# JBC_245.net
KiCad netlist of a schematic drawn in Altium Designer
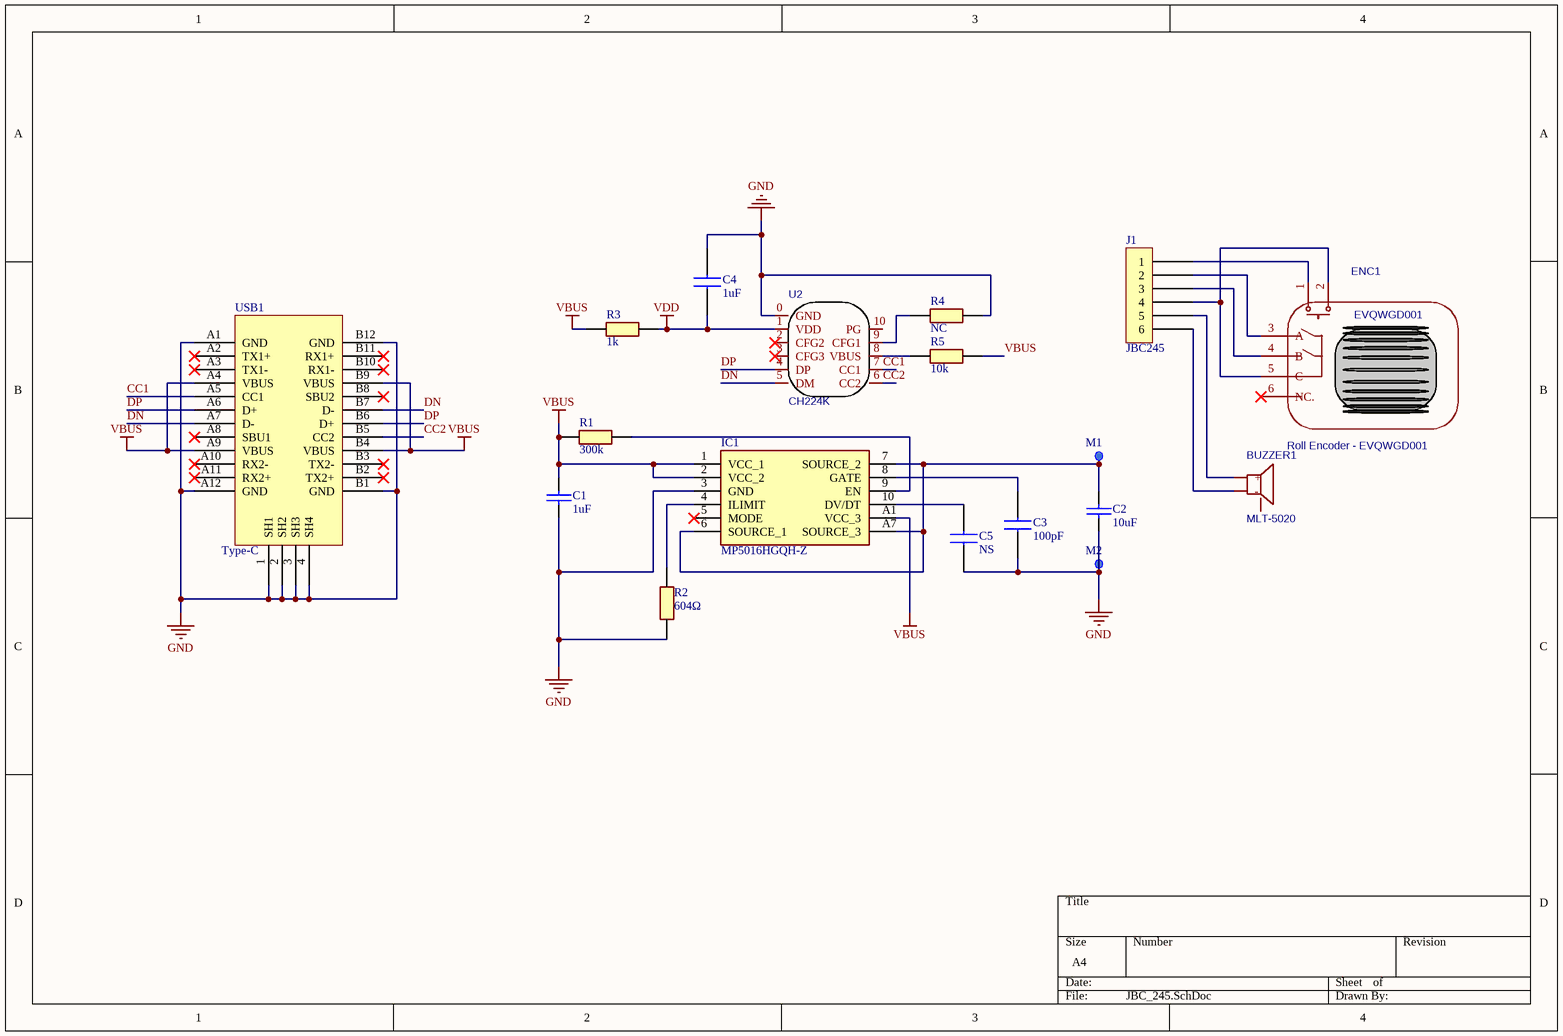
[diagram p0: JBC_245.SchDoc]

(export (version "E")
  (design (tool "Eeschema 10.0.6"))
  (components
    (comp (ref "BUZZER1")
      (value "MLT-5020")
      (footprint "BUZ-SMD_3P-L5.2-W5.2-P3.50-BR")
      (description "Buzzer")
      (fields (field (name "BOM_SUPPLIER PART") "C94598"))
      (libsource (lib "SFT_V4") (part "MLT-5020"))
    )
    (comp (ref "C1")
      (value "1uF")
      (footprint "1206C")
      (description "无极性电容")
      (libsource (lib "电容") (part "CAP"))
    )
    (comp (ref "C2")
      (value "10uF")
      (footprint "1206C")
      (description "无极性电容")
      (libsource (lib "电容") (part "CAP"))
    )
    (comp (ref "C3")
      (value "100pF")
      (footprint "CAP_0402")
      (description "Capacitor")
      (fields
        (field (name "MANUFACTURER_PART_NUMBER") "0402YC104MAT2A")
        (field (name "MOUSER PART NUMBER") "581-0402YC104MAT2A")
      )
      (libsource (lib "SFT_V4") (part "0402YC104MAT2A"))
    )
    (comp (ref "C4")
      (value "1uF")
      (footprint "CAP_0402")
      (description "Capacitor")
      (fields
        (field (name "MANUFACTURER_PART_NUMBER") "0402YC104MAT2A")
        (field (name "MOUSER PART NUMBER") "581-0402YC104MAT2A")
      )
      (libsource (lib "SFT_V4") (part "0402YC104MAT2A"))
    )
    (comp (ref "C5")
      (value "NS")
      (footprint "CAP_0402")
      (description "Capacitor")
      (fields
        (field (name "MANUFACTURER_PART_NUMBER") "0402YC104MAT2A")
        (field (name "MOUSER PART NUMBER") "581-0402YC104MAT2A")
      )
      (libsource (lib "SFT_V4") (part "0402YC104MAT2A"))
    )
    (comp (ref "IC1")
      (value "MP5016HGQH-Z")
      (footprint "MP5016HGQHZ")
      (description "Integrated Circuit")
      (fields (field (name "MOUSER PART NUMBER") "946-MP5016HGQH-Z"))
      (libsource (lib "SFT_V4") (part "MP5016HGQH-Z"))
    )
    (comp (ref "J1")
      (value "JBC245")
      (footprint "JBC_245_Connect")
      (libsource (lib "SFT_V4") (part "JBC_245_Connect"))
    )
    (comp (ref "M1") (value "Test_Point") (footprint "TP-PIN") (libsource (lib "SFT_V4") (part "Test_Point")))
    (comp (ref "M2") (value "Test_Point") (footprint "TP-PIN") (libsource (lib "SFT_V4") (part "Test_Point")))
    (comp (ref "R1")
      (value "300k")
      (footprint "RES_0402")
      (description "Resistor")
      (fields
        (field (name "MANUFACTURER_PART_NUMBER") "RC0402JR-1320RL")
        (field (name "MOUSER PART NUMBER") "603-RC0402JR-1320RL")
      )
      (libsource (lib "") (part "RC0402JR-1320RL_1"))
    )
    (comp (ref "R2")
      (value "604Ω")
      (footprint "RES_0402")
      (description "Resistor")
      (fields
        (field (name "MANUFACTURER_PART_NUMBER") "RC0402JR-1320RL")
        (field (name "MOUSER PART NUMBER") "603-RC0402JR-1320RL")
      )
      (libsource (lib "SFT_V4") (part "RC0402JR-1320RL"))
    )
    (comp (ref "R3")
      (value "1k")
      (footprint "RES_0402")
      (description "Resistor")
      (fields
        (field (name "MANUFACTURER_PART_NUMBER") "RC0402JR-1320RL")
        (field (name "MOUSER PART NUMBER") "603-RC0402JR-1320RL")
      )
      (libsource (lib "") (part "RC0402JR-1320RL_1"))
    )
    (comp (ref "R4")
      (value "NC")
      (footprint "RES_0402")
      (description "Resistor")
      (fields
        (field (name "MANUFACTURER_PART_NUMBER") "RC0402JR-1320RL")
        (field (name "MOUSER PART NUMBER") "603-RC0402JR-1320RL")
      )
      (libsource (lib "") (part "RC0402JR-1320RL_1"))
    )
    (comp (ref "R5")
      (value "10k")
      (footprint "RES_0402")
      (description "Resistor")
      (fields
        (field (name "MANUFACTURER_PART_NUMBER") "RC0402JR-1320RL")
        (field (name "MOUSER PART NUMBER") "603-RC0402JR-1320RL")
      )
      (libsource (lib "") (part "RC0402JR-1320RL_1"))
    )
    (comp (ref "U1")
      (value "Roll Encoder - EVQWGD001")
      (footprint "EVQWGD001 ENCODER")
      (fields (field (name "BOM_MANUFACTURER PART") "EVQWGD001") (field (name "CONTRIBUTOR") "ChristAlix"))
      (libsource (lib "My_AD_Lib") (part "Roll Encoder - EVQWGD001"))
    )
    (comp (ref "U2")
      (value "CH224K")
      (footprint "ESSOP-10_L5.0-W3.9")
      (fields (field (name "CONTRIBUTOR") "小茅"))
      (libsource (lib "My_AD_Lib") (part "CH224K"))
    )
    (comp (ref "USB1")
      (value "Type-C")
      (footprint "Type-C-TOP")
      (libsource (lib "SFT_V4") (part "USB-Type-C-TOP"))
    )
  )
  (nets
    (net (code "1") (name "/CC1") (class "Default")
      (node (ref "U2") (pin "7") (pinfunction "CC1_7") (pintype "passive"))
      (node (ref "USB1") (pin "A5") (pinfunction "CC1_A5") (pintype "passive"))
    )
    (net (code "2") (name "/CC2") (class "Default")
      (node (ref "U2") (pin "6") (pinfunction "CC2_6") (pintype "passive"))
      (node (ref "USB1") (pin "B5") (pinfunction "CC2_B5") (pintype "passive"))
    )
    (net (code "3") (name "/DN") (class "Default")
      (node (ref "U2") (pin "5") (pinfunction "DM_5") (pintype "passive"))
      (node (ref "USB1") (pin "A7") (pinfunction "D-_A7") (pintype "passive"))
      (node (ref "USB1") (pin "B7") (pinfunction "D-_B7") (pintype "passive"))
    )
    (net (code "4") (name "/DP") (class "Default")
      (node (ref "U2") (pin "4") (pinfunction "DP_4") (pintype "passive"))
      (node (ref "USB1") (pin "A6") (pinfunction "D+_A6") (pintype "passive"))
      (node (ref "USB1") (pin "B6") (pinfunction "D+_B6") (pintype "passive"))
    )
    (net (code "5") (name "GND") (class "Default")
      (node (ref "C1") (pin "1") (pinfunction "1_1") (pintype "passive"))
      (node (ref "C2") (pin "1") (pinfunction "1_1") (pintype "passive"))
      (node (ref "C3") (pin "1") (pinfunction "1_1") (pintype "passive"))
      (node (ref "C4") (pin "2") (pinfunction "2_2") (pintype "passive"))
      (node (ref "C5") (pin "1") (pinfunction "1_1") (pintype "passive"))
      (node (ref "IC1") (pin "3") (pinfunction "GND_3") (pintype "passive"))
      (node (ref "M2") (pin "1") (pinfunction "1_1") (pintype "passive"))
      (node (ref "R2") (pin "1") (pinfunction "1_1") (pintype "passive"))
      (node (ref "R4") (pin "2") (pinfunction "2_2") (pintype "passive"))
      (node (ref "U2") (pin "0") (pinfunction "GND_0") (pintype "passive"))
      (node (ref "USB1") (pin "1") (pinfunction "SH1_1") (pintype "passive"))
      (node (ref "USB1") (pin "2") (pinfunction "SH2_2") (pintype "passive"))
      (node (ref "USB1") (pin "3") (pinfunction "SH3_3") (pintype "passive"))
      (node (ref "USB1") (pin "4") (pinfunction "SH4_4") (pintype "passive"))
      (node (ref "USB1") (pin "A1") (pinfunction "GND_A1") (pintype "passive"))
      (node (ref "USB1") (pin "A12") (pinfunction "GND_A12") (pintype "passive"))
      (node (ref "USB1") (pin "B1") (pinfunction "GND_B1") (pintype "passive"))
      (node (ref "USB1") (pin "B12") (pinfunction "GND_B12") (pintype "passive"))
    )
    (net (code "6") (name "Net-(BUZZER1-+)") (class "Default")
      (node (ref "BUZZER1") (pin "2") (pinfunction "+_2") (pintype "passive"))
      (node (ref "J1") (pin "5") (pinfunction "5_5") (pintype "passive"))
    )
    (net (code "7") (name "Net-(BUZZER1--)") (class "Default")
      (node (ref "BUZZER1") (pin "3") (pinfunction "-_3") (pintype "passive"))
      (node (ref "J1") (pin "6") (pinfunction "6_6") (pintype "passive"))
    )
    (net (code "8") (name "Net-(IC1-DV{slash}DT)") (class "Default")
      (node (ref "C5") (pin "2") (pinfunction "2_2") (pintype "passive"))
      (node (ref "IC1") (pin "10") (pinfunction "DV/DT_10") (pintype "passive"))
    )
    (net (code "9") (name "Net-(IC1-EN)") (class "Default")
      (node (ref "IC1") (pin "9") (pinfunction "EN_9") (pintype "passive"))
      (node (ref "R1") (pin "2") (pinfunction "2_2") (pintype "passive"))
    )
    (net (code "10") (name "Net-(IC1-GATE)") (class "Default")
      (node (ref "C3") (pin "2") (pinfunction "2_2") (pintype "passive"))
      (node (ref "IC1") (pin "8") (pinfunction "GATE_8") (pintype "passive"))
    )
    (net (code "11") (name "Net-(IC1-ILIMIT)") (class "Default")
      (node (ref "IC1") (pin "4") (pinfunction "ILIMIT_4") (pintype "passive"))
      (node (ref "R2") (pin "2") (pinfunction "2_2") (pintype "passive"))
    )
    (net (code "12") (name "Net-(IC1-SOURCE_1)") (class "Default")
      (node (ref "C2") (pin "2") (pinfunction "2_2") (pintype "passive"))
      (node (ref "IC1") (pin "6") (pinfunction "SOURCE_1_6") (pintype "passive"))
      (node (ref "IC1") (pin "7") (pinfunction "SOURCE_2_7") (pintype "passive"))
      (node (ref "IC1") (pin "A7") (pinfunction "SOURCE_3_A7") (pintype "passive"))
      (node (ref "M1") (pin "1") (pinfunction "1_1") (pintype "passive"))
    )
    (net (code "13") (name "Net-(U1-A)") (class "Default")
      (node (ref "J1") (pin "2") (pinfunction "2_2") (pintype "passive"))
      (node (ref "U1") (pin "3") (pinfunction "A_3") (pintype "passive"))
    )
    (net (code "14") (name "Net-(U1-B)") (class "Default")
      (node (ref "J1") (pin "3") (pinfunction "3_3") (pintype "passive"))
      (node (ref "U1") (pin "4") (pinfunction "B_4") (pintype "passive"))
    )
    (net (code "15") (name "Net-(U1-C)") (class "Default")
      (node (ref "J1") (pin "4") (pinfunction "4_4") (pintype "passive"))
      (node (ref "U1") (pin "2") (pinfunction "SW2_2") (pintype "passive"))
      (node (ref "U1") (pin "5") (pinfunction "C_5") (pintype "passive"))
    )
    (net (code "16") (name "Net-(U1-SW1)") (class "Default")
      (node (ref "J1") (pin "1") (pinfunction "1_1") (pintype "passive"))
      (node (ref "U1") (pin "1") (pinfunction "SW1_1") (pintype "passive"))
    )
    (net (code "17") (name "Net-(U2-CFG1)") (class "Default")
      (node (ref "R4") (pin "1") (pinfunction "1_1") (pintype "passive"))
      (node (ref "U2") (pin "9") (pinfunction "CFG1_9") (pintype "passive"))
    )
    (net (code "18") (name "Net-(U2-VBUS)") (class "Default")
      (node (ref "R5") (pin "1") (pinfunction "1_1") (pintype "passive"))
      (node (ref "U2") (pin "8") (pinfunction "VBUS_8") (pintype "passive"))
    )
    (net (code "19") (name "VBUS") (class "Default")
      (node (ref "C1") (pin "2") (pinfunction "2_2") (pintype "passive"))
      (node (ref "IC1") (pin "1") (pinfunction "VCC_1_1") (pintype "passive"))
      (node (ref "IC1") (pin "2") (pinfunction "VCC_2_2") (pintype "passive"))
      (node (ref "IC1") (pin "A1") (pinfunction "VCC_3_A1") (pintype "passive"))
      (node (ref "R1") (pin "1") (pinfunction "1_1") (pintype "passive"))
      (node (ref "R3") (pin "1") (pinfunction "1_1") (pintype "passive"))
      (node (ref "R5") (pin "2") (pinfunction "2_2") (pintype "passive"))
      (node (ref "USB1") (pin "A4") (pinfunction "VBUS_A4") (pintype "passive"))
      (node (ref "USB1") (pin "A9") (pinfunction "VBUS_A9") (pintype "passive"))
      (node (ref "USB1") (pin "B4") (pinfunction "VBUS_B4") (pintype "passive"))
      (node (ref "USB1") (pin "B9") (pinfunction "VBUS_B9") (pintype "passive"))
    )
    (net (code "20") (name "VDD") (class "Default")
      (node (ref "C4") (pin "1") (pinfunction "1_1") (pintype "passive"))
      (node (ref "R3") (pin "2") (pinfunction "2_2") (pintype "passive"))
      (node (ref "U2") (pin "1") (pinfunction "VDD_1") (pintype "passive"))
    )
    (net (code "21") (name "unconnected-(BUZZER1-NC-Pad1)") (class "Default")
      (node (ref "BUZZER1") (pin "1") (pinfunction "NC_1") (pintype "passive"))
    )
    (net (code "22") (name "unconnected-(IC1-MODE-Pad5)") (class "Default")
      (node (ref "IC1") (pin "5") (pinfunction "MODE_5") (pintype "passive+no_connect"))
    )
    (net (code "23") (name "unconnected-(U1-NC.-Pad6)") (class "Default")
      (node (ref "U1") (pin "6") (pinfunction "NC._6") (pintype "passive+no_connect"))
    )
    (net (code "24") (name "unconnected-(U2-CFG2-Pad2)") (class "Default")
      (node (ref "U2") (pin "2") (pinfunction "CFG2_2") (pintype "passive+no_connect"))
    )
    (net (code "25") (name "unconnected-(U2-CFG3-Pad3)") (class "Default")
      (node (ref "U2") (pin "3") (pinfunction "CFG3_3") (pintype "passive+no_connect"))
    )
    (net (code "26") (name "unconnected-(U2-PG-Pad10)") (class "Default")
      (node (ref "U2") (pin "10") (pinfunction "PG_10") (pintype "passive"))
    )
    (net (code "27") (name "unconnected-(USB1-RX1+-PadB11)") (class "Default")
      (node (ref "USB1") (pin "B11") (pinfunction "RX1+_B11") (pintype "passive+no_connect"))
    )
    (net (code "28") (name "unconnected-(USB1-RX1--PadB10)") (class "Default")
      (node (ref "USB1") (pin "B10") (pinfunction "RX1-_B10") (pintype "passive+no_connect"))
    )
    (net (code "29") (name "unconnected-(USB1-RX2+-PadA11)") (class "Default")
      (node (ref "USB1") (pin "A11") (pinfunction "RX2+_A11") (pintype "passive+no_connect"))
    )
    (net (code "30") (name "unconnected-(USB1-RX2--PadA10)") (class "Default")
      (node (ref "USB1") (pin "A10") (pinfunction "RX2-_A10") (pintype "passive+no_connect"))
    )
    (net (code "31") (name "unconnected-(USB1-SBU1-PadA8)") (class "Default")
      (node (ref "USB1") (pin "A8") (pinfunction "SBU1_A8") (pintype "passive+no_connect"))
    )
    (net (code "32") (name "unconnected-(USB1-SBU2-PadB8)") (class "Default")
      (node (ref "USB1") (pin "B8") (pinfunction "SBU2_B8") (pintype "passive+no_connect"))
    )
    (net (code "33") (name "unconnected-(USB1-TX1+-PadA2)") (class "Default")
      (node (ref "USB1") (pin "A2") (pinfunction "TX1+_A2") (pintype "passive+no_connect"))
    )
    (net (code "34") (name "unconnected-(USB1-TX1--PadA3)") (class "Default")
      (node (ref "USB1") (pin "A3") (pinfunction "TX1-_A3") (pintype "passive+no_connect"))
    )
    (net (code "35") (name "unconnected-(USB1-TX2+-PadB2)") (class "Default")
      (node (ref "USB1") (pin "B2") (pinfunction "TX2+_B2") (pintype "passive+no_connect"))
    )
    (net (code "36") (name "unconnected-(USB1-TX2--PadB3)") (class "Default")
      (node (ref "USB1") (pin "B3") (pinfunction "TX2-_B3") (pintype "passive+no_connect"))
    )
  )
)
